# newDCDCMirror.net
KiCad netlist of a schematic drawn in EAGLE
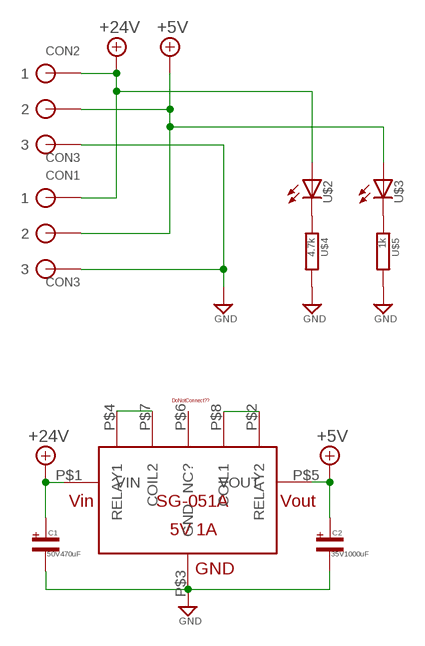
[diagram p0: schematic, sheet 1]

(export (version "E")
  (design (tool "Eeschema 10.0.6"))
  (components
    (comp (ref "C1")
      (value "50V470uF")
      (footprint "eagle-import:D=2,φ=10,5")
      (libsource (lib "eagle-import") (part "コンデンサ(電解)E5-10.5"))
    )
    (comp (ref "C2")
      (value "35V1000uF")
      (footprint "eagle-import:D=2,φ=13")
      (libsource (lib "eagle-import") (part "コンデンサ(電解)E5-13"))
    )
    (comp (ref "CON1")
      (value "CON3")
      (footprint "eagle-import:CON3")
      (libsource (lib "eagle-import") (part "CON3"))
    )
    (comp (ref "CON2")
      (value "CON3")
      (footprint "eagle-import:CON3")
      (libsource (lib "eagle-import") (part "CON3"))
    )
    (comp (ref "U$1")
      (value "SG-051A")
      (footprint "eagle-import:SG-051A")
      (libsource (lib "eagle-import") (part "SG-051A"))
    )
    (comp (ref "U$2")
      (value "LED(砲弾型)3")
      (footprint "eagle-import:LED3MM")
      (libsource (lib "eagle-import") (part "LED(砲弾型)3"))
    )
    (comp (ref "U$3")
      (value "LED(砲弾型)3")
      (footprint "eagle-import:LED3MM")
      (libsource (lib "eagle-import") (part "LED(砲弾型)3"))
    )
    (comp (ref "U$4")
      (value "4.7k")
      (footprint "eagle-import:0805")
      (libsource (lib "eagle-import") (part "抵抗0805"))
    )
    (comp (ref "U$5")
      (value "1k")
      (footprint "eagle-import:0805")
      (libsource (lib "eagle-import") (part "抵抗0805"))
    )
  )
  (nets
    (net (code "1") (name "+5V") (class "Default")
      (node (ref "C2") (pin "+") (pinfunction "+_+") (pintype "passive"))
      (node (ref "CON1") (pin "P$2") (pinfunction "2_P$2") (pintype "bidirectional"))
      (node (ref "CON2") (pin "P$2") (pinfunction "2_P$2") (pintype "bidirectional"))
      (node (ref "U$1") (pin "P$5") (pinfunction "VOUT_P$5") (pintype "bidirectional"))
      (node (ref "U$3") (pin "A") (pinfunction "A_A") (pintype "passive"))
    )
    (net (code "2") (name "+24V") (class "Default")
      (node (ref "C1") (pin "+") (pinfunction "+_+") (pintype "passive"))
      (node (ref "CON1") (pin "P$1") (pinfunction "1_P$1") (pintype "bidirectional"))
      (node (ref "CON2") (pin "P$1") (pinfunction "1_P$1") (pintype "bidirectional"))
      (node (ref "U$1") (pin "P$1") (pinfunction "VIN_P$1") (pintype "bidirectional"))
      (node (ref "U$2") (pin "A") (pinfunction "A_A") (pintype "passive"))
    )
    (net (code "3") (name "GND") (class "Default")
      (node (ref "C1") (pin "-") (pinfunction "-_-") (pintype "passive"))
      (node (ref "C2") (pin "-") (pinfunction "-_-") (pintype "passive"))
      (node (ref "CON1") (pin "P$3") (pinfunction "3_P$3") (pintype "bidirectional"))
      (node (ref "CON2") (pin "P$3") (pinfunction "3_P$3") (pintype "bidirectional"))
      (node (ref "U$1") (pin "P$3") (pinfunction "GND_P$3") (pintype "bidirectional"))
      (node (ref "U$4") (pin "2") (pinfunction "2_2") (pintype "passive"))
      (node (ref "U$5") (pin "2") (pinfunction "2_2") (pintype "passive"))
    )
    (net (code "4") (name "Net-(U$1-COIL1)") (class "Default")
      (node (ref "U$1") (pin "P$2") (pinfunction "RELAY2_P$2") (pintype "bidirectional"))
      (node (ref "U$1") (pin "P$8") (pinfunction "COIL1_P$8") (pintype "bidirectional"))
    )
    (net (code "5") (name "Net-(U$1-COIL2)") (class "Default")
      (node (ref "U$1") (pin "P$4") (pinfunction "RELAY1_P$4") (pintype "bidirectional"))
      (node (ref "U$1") (pin "P$7") (pinfunction "COIL2_P$7") (pintype "bidirectional"))
    )
    (net (code "6") (name "Net-(U$2-PadK)") (class "Default")
      (node (ref "U$2") (pin "K") (pinfunction "K_K") (pintype "passive"))
      (node (ref "U$4") (pin "1") (pinfunction "1_1") (pintype "passive"))
    )
    (net (code "7") (name "Net-(U$3-PadK)") (class "Default")
      (node (ref "U$3") (pin "K") (pinfunction "K_K") (pintype "passive"))
      (node (ref "U$5") (pin "1") (pinfunction "1_1") (pintype "passive"))
    )
    (net (code "8") (name "unconnected-(U$1-NC?-PadP$6)") (class "Default")
      (node (ref "U$1") (pin "P$6") (pinfunction "NC?_P$6") (pintype "bidirectional"))
    )
  )
)
